# WiFi_CC3000MOD.net
KiCad netlist of a schematic drawn in Altium Designer
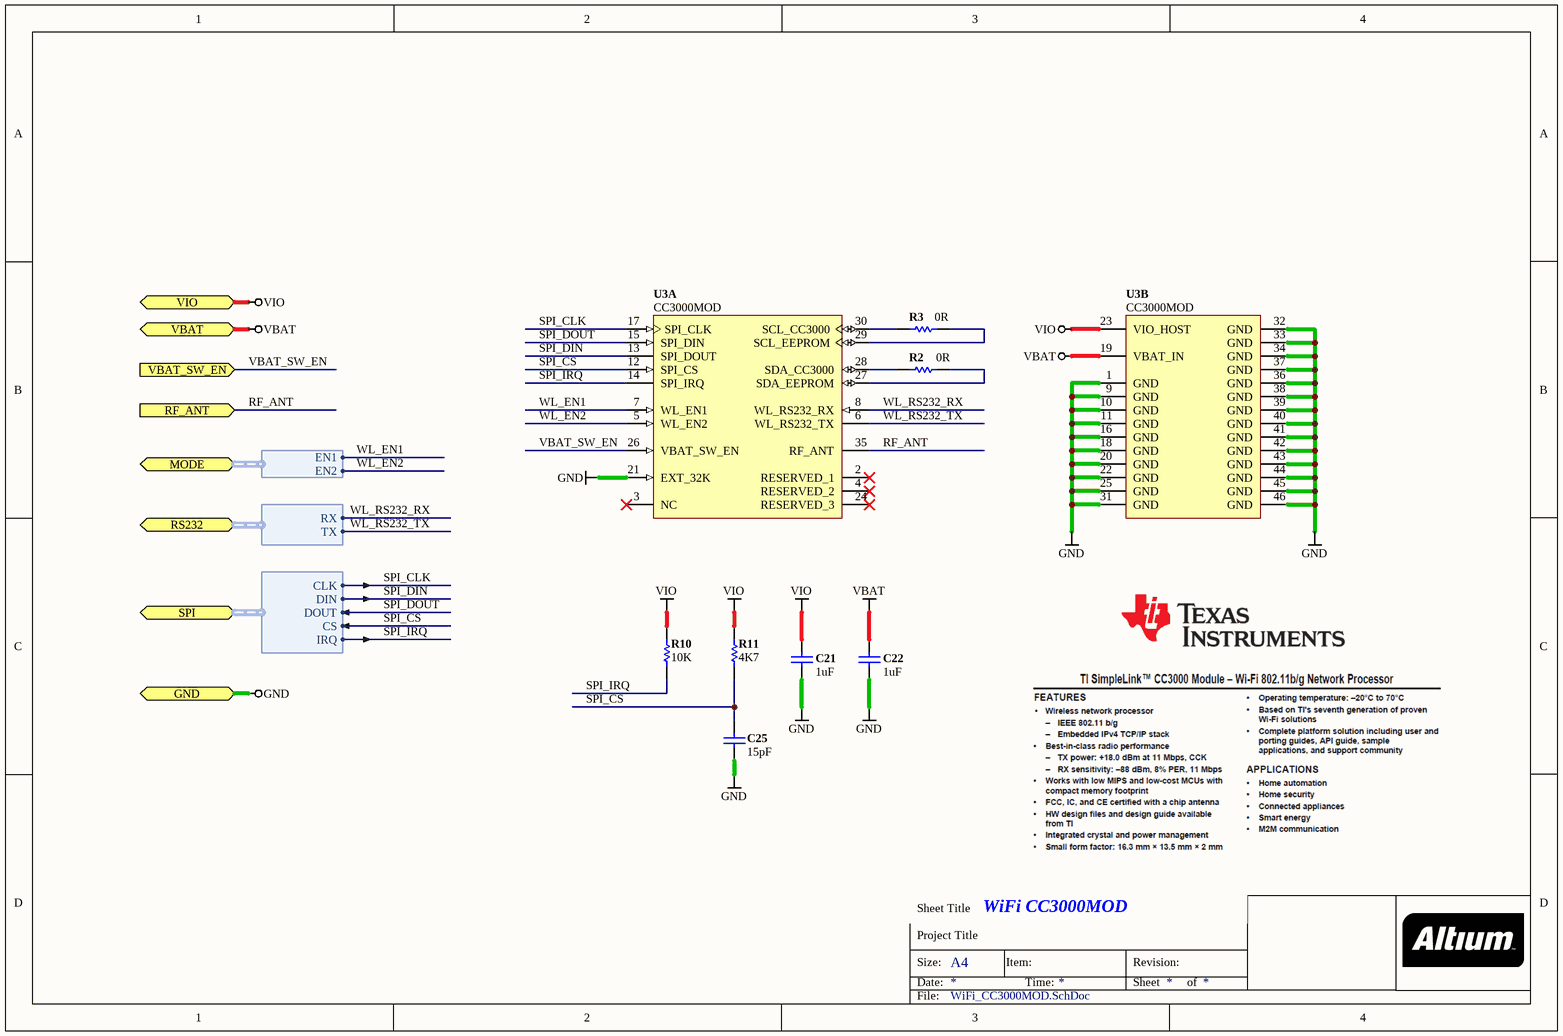
[diagram p0: WiFi_CC3000MOD.SchDoc]

(export (version "E")
  (design (tool "Eeschema 10.0.6"))
  (components
    (comp (ref "C21")
      (value "1uF")
      (footprint "CAPC0603(1608)100_L")
      (description "CAP 1uF 10V ±10% 0603 (1608 Metric) Thickness 1mm SMD")
      (fields (field (name "TOLERANCE") "±10%") (field (name "Comment") "CAP 1uF 10V 0603(1608)"))
      (libsource (lib "Altium Content Vault") (part "CMP-1035-02733-1"))
    )
    (comp (ref "C22")
      (value "1uF")
      (footprint "CAPC0603(1608)100_L")
      (description "CAP 1uF 10V ±10% 0603 (1608 Metric) Thickness 1mm SMD")
      (fields (field (name "TOLERANCE") "±10%") (field (name "Comment") "CAP 1uF 10V 0603(1608)"))
      (libsource (lib "Altium Content Vault") (part "CMP-1035-02733-1"))
    )
    (comp (ref "C25")
      (value "15pF")
      (footprint "CAPC0603(1608)100_L")
      (description "CAP 15pF 10V ±5% 0603 (1608 Metric) Thickness 1mm SMD")
      (fields (field (name "TOLERANCE") "±5%") (field (name "Comment") "CAP 15pF 10V 0603(1608)"))
      (libsource (lib "Altium Content Vault") (part "CMP-1035-00662-1"))
    )
    (comp (ref "R2")
      (value "0R")
      (footprint "RESC0402(1005)_L")
      (description "Jumper 0402 (1005 Metric)")
      (fields (field (name "TOLERANCE") "None"))
      (libsource (lib "Altium Content Vault") (part "CMP-1011-00001-1"))
    )
    (comp (ref "R3")
      (value "0R")
      (footprint "RESC0402(1005)_L")
      (description "Jumper 0402 (1005 Metric)")
      (fields (field (name "TOLERANCE") "None"))
      (libsource (lib "Altium Content Vault") (part "CMP-1011-00001-1"))
    )
    (comp (ref "R10")
      (value "10K")
      (footprint "RESC0603(1608)_L")
      (description "10K 0.1W 5% 0603 (1608 Metric)  SMD")
      (fields (field (name "TOLERANCE") "5 %") (field (name "POWER") "0.1 W"))
      (libsource (lib "Altium Content Vault") (part "CMP-1012-00098-1"))
    )
    (comp (ref "R11")
      (value "4K7")
      (footprint "RESC0603(1608)_L")
      (description "4K7 0.1W 5% 0603 (1608 Metric)  SMD")
      (fields (field (name "TOLERANCE") "5 %") (field (name "POWER") "0.1 W"))
      (libsource (lib "Altium Content Vault") (part "CMP-1012-00090-1"))
    )
    (comp (ref "U3")
      (value "CC3000MOD")
      (footprint "TI-CC3000MOD-46_V")
      (description "SimpleLink Wi-Fi Module")
      (fields (field (name "MANUFACTURER") "Texas Instruments"))
      (libsource (lib "Altium Content Vault") (part "TI-CC3000MOD-46"))
    )
  )
  (nets
    (net (code "4") (name "/RF_ANT") (class "Default")
      (node (ref "U3") (pin "35") (pinfunction "RF_ANT_35") (pintype "passive"))
    )
    (net (code "5") (name "/SPI_CLK") (class "Default")
      (node (ref "U3") (pin "17") (pinfunction "SPI_CLK_17") (pintype "input"))
    )
    (net (code "6") (name "/SPI_CS") (class "Default")
      (node (ref "C25") (pin "2") (pinfunction "2_2") (pintype "passive"))
      (node (ref "R11") (pin "1") (pinfunction "1_1") (pintype "passive"))
      (node (ref "U3") (pin "12") (pinfunction "SPI_CS_12") (pintype "input"))
    )
    (net (code "7") (name "/SPI_DIN") (class "Default")
      (node (ref "U3") (pin "13") (pinfunction "SPI_DOUT_13") (pintype "tri_state"))
    )
    (net (code "8") (name "/SPI_DOUT") (class "Default")
      (node (ref "U3") (pin "15") (pinfunction "SPI_DIN_15") (pintype "input"))
    )
    (net (code "9") (name "/SPI_IRQ") (class "Default")
      (node (ref "R10") (pin "1") (pinfunction "1_1") (pintype "passive"))
      (node (ref "U3") (pin "14") (pinfunction "SPI_IRQ_14") (pintype "tri_state"))
    )
    (net (code "10") (name "/VBAT_SW_EN") (class "Default")
      (node (ref "U3") (pin "26") (pinfunction "VBAT_SW_EN_26") (pintype "input"))
    )
    (net (code "11") (name "/WL_EN1") (class "Default")
      (node (ref "U3") (pin "7") (pinfunction "WL_EN1_7") (pintype "input"))
    )
    (net (code "12") (name "/WL_EN2") (class "Default")
      (node (ref "U3") (pin "5") (pinfunction "WL_EN2_5") (pintype "input"))
    )
    (net (code "13") (name "/WL_RS232_RX") (class "Default")
      (node (ref "U3") (pin "8") (pinfunction "WL_RS232_RX_8") (pintype "input"))
    )
    (net (code "14") (name "/WL_RS232_TX") (class "Default")
      (node (ref "U3") (pin "6") (pinfunction "WL_RS232_TX_6") (pintype "tri_state"))
    )
    (net (code "18") (name "GND") (class "Default")
      (node (ref "C21") (pin "1") (pinfunction "1_1") (pintype "passive"))
      (node (ref "C22") (pin "1") (pinfunction "1_1") (pintype "passive"))
      (node (ref "C25") (pin "1") (pinfunction "1_1") (pintype "passive"))
      (node (ref "U3") (pin "1") (pinfunction "GND_1") (pintype "power_in"))
      (node (ref "U3") (pin "10") (pinfunction "GND_10") (pintype "power_in"))
      (node (ref "U3") (pin "11") (pinfunction "GND_11") (pintype "power_in"))
      (node (ref "U3") (pin "16") (pinfunction "GND_16") (pintype "power_in"))
      (node (ref "U3") (pin "18") (pinfunction "GND_18") (pintype "power_in"))
      (node (ref "U3") (pin "20") (pinfunction "GND_20") (pintype "power_in"))
      (node (ref "U3") (pin "21") (pinfunction "EXT_32K_21") (pintype "input"))
      (node (ref "U3") (pin "22") (pinfunction "GND_22") (pintype "power_in"))
      (node (ref "U3") (pin "25") (pinfunction "GND_25") (pintype "power_in"))
      (node (ref "U3") (pin "31") (pinfunction "GND_31") (pintype "power_in"))
      (node (ref "U3") (pin "32") (pinfunction "GND_32") (pintype "power_in"))
      (node (ref "U3") (pin "33") (pinfunction "GND_33") (pintype "power_in"))
      (node (ref "U3") (pin "34") (pinfunction "GND_34") (pintype "power_in"))
      (node (ref "U3") (pin "36") (pinfunction "GND_36") (pintype "power_in"))
      (node (ref "U3") (pin "37") (pinfunction "GND_37") (pintype "power_in"))
      (node (ref "U3") (pin "38") (pinfunction "GND_38") (pintype "power_in"))
      (node (ref "U3") (pin "39") (pinfunction "GND_39") (pintype "power_in"))
      (node (ref "U3") (pin "40") (pinfunction "GND_40") (pintype "power_in"))
      (node (ref "U3") (pin "41") (pinfunction "GND_41") (pintype "power_in"))
      (node (ref "U3") (pin "42") (pinfunction "GND_42") (pintype "power_in"))
      (node (ref "U3") (pin "43") (pinfunction "GND_43") (pintype "power_in"))
      (node (ref "U3") (pin "44") (pinfunction "GND_44") (pintype "power_in"))
      (node (ref "U3") (pin "45") (pinfunction "GND_45") (pintype "power_in"))
      (node (ref "U3") (pin "46") (pinfunction "GND_46") (pintype "power_in"))
      (node (ref "U3") (pin "9") (pinfunction "GND_9") (pintype "power_in"))
    )
    (net (code "19") (name "Net-(U3A-SCL_CC3000)") (class "Default")
      (node (ref "R3") (pin "1") (pinfunction "1_1") (pintype "passive"))
      (node (ref "U3") (pin "30") (pinfunction "SCL_CC3000_30") (pintype "bidirectional"))
    )
    (net (code "20") (name "Net-(U3A-SCL_EEPROM)") (class "Default")
      (node (ref "R3") (pin "2") (pinfunction "2_2") (pintype "passive"))
      (node (ref "U3") (pin "29") (pinfunction "SCL_EEPROM_29") (pintype "bidirectional"))
    )
    (net (code "21") (name "Net-(U3A-SDA_CC3000)") (class "Default")
      (node (ref "R2") (pin "1") (pinfunction "1_1") (pintype "passive"))
      (node (ref "U3") (pin "28") (pinfunction "SDA_CC3000_28") (pintype "bidirectional"))
    )
    (net (code "22") (name "Net-(U3A-SDA_EEPROM)") (class "Default")
      (node (ref "R2") (pin "2") (pinfunction "2_2") (pintype "passive"))
      (node (ref "U3") (pin "27") (pinfunction "SDA_EEPROM_27") (pintype "bidirectional"))
    )
    (net (code "23") (name "VBAT") (class "Default")
      (node (ref "C22") (pin "2") (pinfunction "2_2") (pintype "passive"))
      (node (ref "U3") (pin "19") (pinfunction "VBAT_IN_19") (pintype "power_in"))
    )
    (net (code "24") (name "VIO") (class "Default")
      (node (ref "C21") (pin "2") (pinfunction "2_2") (pintype "passive"))
      (node (ref "R10") (pin "2") (pinfunction "2_2") (pintype "passive"))
      (node (ref "R11") (pin "2") (pinfunction "2_2") (pintype "passive"))
      (node (ref "U3") (pin "23") (pinfunction "VIO_HOST_23") (pintype "power_in"))
    )
    (net (code "25") (name "unconnected-(U3A-NC-Pad3)") (class "Default")
      (node (ref "U3") (pin "3") (pinfunction "NC_3") (pintype "passive+no_connect"))
    )
    (net (code "26") (name "unconnected-(U3A-RESERVED_1-Pad2)") (class "Default")
      (node (ref "U3") (pin "2") (pinfunction "RESERVED_1_2") (pintype "passive+no_connect"))
    )
    (net (code "27") (name "unconnected-(U3A-RESERVED_2-Pad4)") (class "Default")
      (node (ref "U3") (pin "4") (pinfunction "RESERVED_2_4") (pintype "passive+no_connect"))
    )
    (net (code "28") (name "unconnected-(U3A-RESERVED_3-Pad24)") (class "Default")
      (node (ref "U3") (pin "24") (pinfunction "RESERVED_3_24") (pintype "passive+no_connect"))
    )
  )
)
